# Schematic.net
KiCad netlist of a schematic drawn in Altium Designer
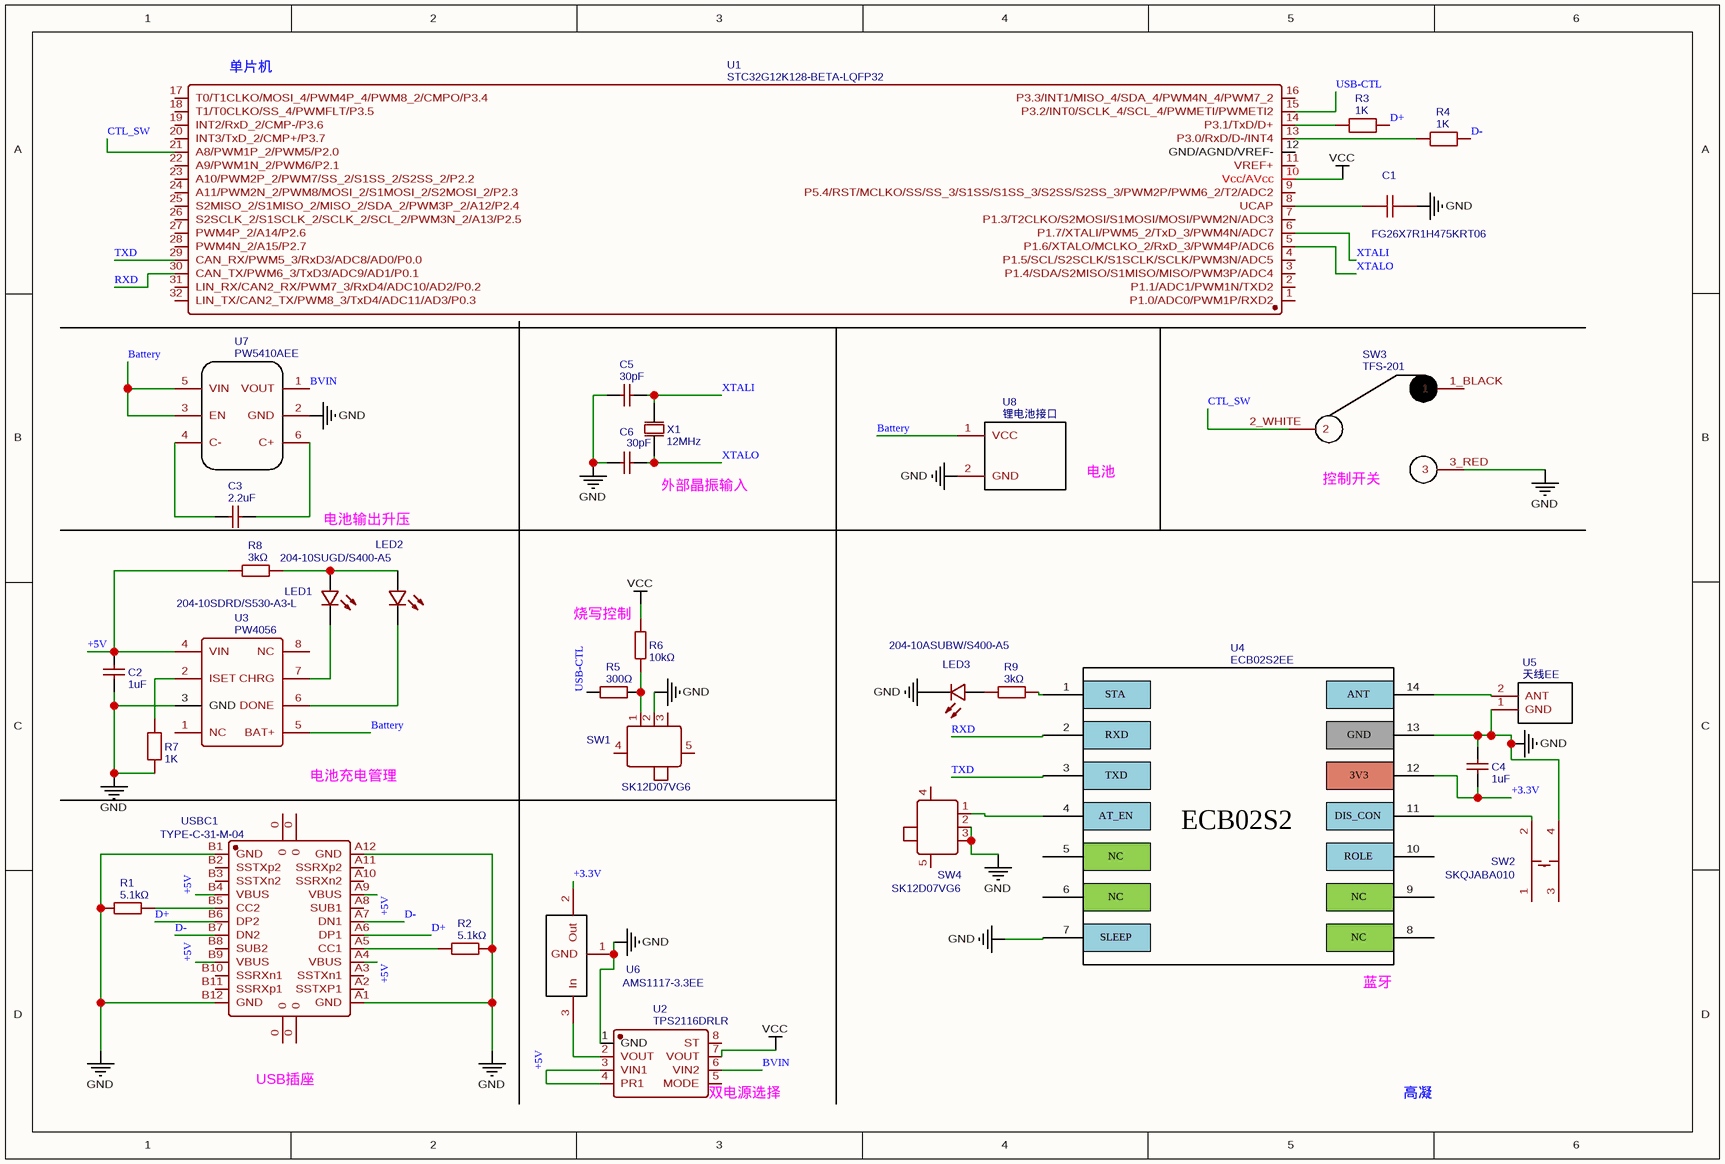
[diagram p0: Schematic原理图.schdoc]

(export (version "E")
  (design (tool "Eeschema 10.0.6"))
  (components
    (comp (ref "C1")
      (value "FG26X7R1H475KRT06")
      (fields (field (name "BOM_SUPPLIER PART") "C1620752") (field (name "CONTRIBUTOR") "LCSC"))
      (libsource (lib "altium-import") (part "root_0_FG26X7R1H475KRT06_"))
    )
    (comp (ref "C2")
      (value "1uF")
      (fields
        (field (name "BOM_MANUFACTURER PART") "CT4-0805B105K500F3")
        (field (name "BOM_SUPPLIER PART") "C94708")
        (field (name "CONTRIBUTOR") "LCSC")
      )
      (libsource (lib "altium-import") (part "root_1_1uF_"))
    )
    (comp (ref "C3")
      (value "2.2uF")
      (fields
        (field (name "BOM_SUPPLIER PART") "C263178")
        (field (name "BOM_MANUFACTURER PART") "CD1E225KC9BER1E000")
        (field (name "CONTRIBUTOR") "LCSC")
      )
      (libsource (lib "altium-import") (part "root_0_2.2uF_"))
    )
    (comp (ref "C4")
      (value "1uF")
      (fields
        (field (name "BOM_MANUFACTURER PART") "CT4-0805B105K500F3")
        (field (name "BOM_SUPPLIER PART") "C94708")
        (field (name "CONTRIBUTOR") "LCSC")
      )
      (libsource (lib "altium-import") (part "root_1_1uF_"))
    )
    (comp (ref "C5")
      (value "30pF")
      (fields
        (field (name "BOM_SUPPLIER PART") "C263194")
        (field (name "BOM_MANUFACTURER PART") "CD1H300JC94ECHD000")
        (field (name "CONTRIBUTOR") "LCSC")
      )
      (libsource (lib "altium-import") (part "root_0_30pF_"))
    )
    (comp (ref "C6")
      (value "30pF")
      (fields
        (field (name "BOM_SUPPLIER PART") "C263194")
        (field (name "BOM_MANUFACTURER PART") "CD1H300JC94ECHD000")
        (field (name "CONTRIBUTOR") "LCSC")
      )
      (libsource (lib "altium-import") (part "root_2_30pF_"))
    )
    (comp (ref "LED1")
      (value "204-10SDRD/S530-A3-L")
      (fields (field (name "BOM_SUPPLIER PART") "C84774"))
      (libsource (lib "altium-import") (part "root_3_204-10SDRD/S530-A3-L_"))
    )
    (comp (ref "LED2")
      (value "204-10SUGD/S400-A5")
      (fields (field (name "BOM_SUPPLIER PART") "C99761"))
      (libsource (lib "altium-import") (part "root_3_204-10SUGD/S400-A5_"))
    )
    (comp (ref "LED3")
      (value "204-10ASUBW/S400-A5")
      (fields (field (name "BOM_SUPPLIER PART") "C97696"))
      (libsource (lib "altium-import") (part "root_2_204-10ASUBW/S400-A5_"))
    )
    (comp (ref "R1")
      (value "5.1kΩ")
      (fields
        (field (name "BOM_SUPPLIER PART") "C119887")
        (field (name "BOM_MANUFACTURER PART") "CF1/6W-5.1KΩ±5% T")
        (field (name "CONTRIBUTOR") "LCSC")
      )
      (libsource (lib "altium-import") (part "root_0_5.1kΩ_"))
    )
    (comp (ref "R2")
      (value "5.1kΩ")
      (fields
        (field (name "BOM_SUPPLIER PART") "C119887")
        (field (name "BOM_MANUFACTURER PART") "CF1/6W-5.1KΩ±5% T")
        (field (name "CONTRIBUTOR") "LCSC")
      )
      (libsource (lib "altium-import") (part "root_0_5.1kΩ_"))
    )
    (comp (ref "R3")
      (value "1K")
      (fields
        (field (name "BOM_SUPPLIER PART") "C2979794")
        (field (name "BOM_MANUFACTURER PART") "MRS25000C1001FCT00")
        (field (name "CONTRIBUTOR") "lcsc")
      )
      (libsource (lib "altium-import") (part "root_2_1K_"))
    )
    (comp (ref "R4")
      (value "1K")
      (fields
        (field (name "BOM_SUPPLIER PART") "C2979794")
        (field (name "BOM_MANUFACTURER PART") "MRS25000C1001FCT00")
        (field (name "CONTRIBUTOR") "lcsc")
      )
      (libsource (lib "altium-import") (part "root_2_1K_"))
    )
    (comp (ref "R5")
      (value "300Ω")
      (fields
        (field (name "BOM_MANUFACTURER PART") "MFR0W4F3000A50")
        (field (name "BOM_SUPPLIER PART") "C58609")
      )
      (libsource (lib "altium-import") (part "root_0_300Ω_"))
    )
    (comp (ref "R6")
      (value "10kΩ")
      (fields
        (field (name "BOM_SUPPLIER PART") "C2843070")
        (field (name "BOM_MANUFACTURER PART") "MO2WS-10K±5%-6T63")
        (field (name "CONTRIBUTOR") "lcsc")
      )
      (libsource (lib "altium-import") (part "root_1_10kΩ_"))
    )
    (comp (ref "R7")
      (value "1K")
      (fields
        (field (name "BOM_SUPPLIER PART") "C2979794")
        (field (name "BOM_MANUFACTURER PART") "MRS25000C1001FCT00")
        (field (name "CONTRIBUTOR") "lcsc")
      )
      (libsource (lib "altium-import") (part "root_1_1K_"))
    )
    (comp (ref "R8")
      (value "3kΩ")
      (fields
        (field (name "BOM_SUPPLIER PART") "C119881")
        (field (name "BOM_MANUFACTURER PART") "CF1/6W-3KΩ±5% T")
        (field (name "CONTRIBUTOR") "LCSC")
      )
      (libsource (lib "altium-import") (part "root_0_3kΩ_"))
    )
    (comp (ref "R9")
      (value "3kΩ")
      (fields
        (field (name "BOM_SUPPLIER PART") "C119881")
        (field (name "BOM_MANUFACTURER PART") "CF1/6W-3KΩ±5% T")
        (field (name "CONTRIBUTOR") "LCSC")
      )
      (libsource (lib "altium-import") (part "root_0_3kΩ_"))
    )
    (comp (ref "SW1")
      (value "SK12D07VG6")
      (fields (field (name "BOM_SUPPLIER PART") "C2681575") (field (name "CONTRIBUTOR") "LCSC"))
      (libsource (lib "altium-import") (part "root_0_SK12D07VG6_"))
    )
    (comp (ref "SW2")
      (value "SKQJABA010")
      (fields (field (name "BOM_SUPPLIER PART") "C125037") (field (name "CONTRIBUTOR") "LCSC"))
      (libsource (lib "altium-import") (part "root_1_SKQJABA010_"))
    )
    (comp (ref "SW3")
      (value "TFS-201")
      (fields (field (name "CONTRIBUTOR") "watcem"))
      (libsource (lib "altium-import") (part "root_0_TFS-201_"))
    )
    (comp (ref "SW4")
      (value "SK12D07VG6")
      (fields (field (name "BOM_SUPPLIER PART") "C2681575") (field (name "CONTRIBUTOR") "LCSC"))
      (libsource (lib "altium-import") (part "root_3_SK12D07VG6_"))
    )
    (comp (ref "U1")
      (value "STC32G12K128-BETA-LQFP32")
      (fields
        (field (name "BOM_SUPPLIER PART") "C3020369")
        (field (name "BOM_MANUFACTURER PART") "STC32G12K128-Beta-LQFP32")
        (field (name "CONTRIBUTOR") "lcsc")
      )
      (libsource (lib "altium-import") (part "root_2_STC32G12K128-BETA-LQFP32_"))
    )
    (comp (ref "U2")
      (value "TPS2116DRLR")
      (fields (field (name "BOM_SUPPLIER PART") "C3235557") (field (name "CONTRIBUTOR") "lcsc"))
      (libsource (lib "altium-import") (part "root_0_TPS2116DRLR_"))
    )
    (comp (ref "U3")
      (value "PW4056")
      (fields (field (name "CONTRIBUTOR") "Poyzb"))
      (libsource (lib "altium-import") (part "root_0_PW4056_"))
    )
    (comp (ref "U4")
      (value "ECB02S2EE")
      (fields (field (name "CONTRIBUTOR") "fenghongchang"))
      (libsource (lib "altium-import") (part "root_0_ECB02S2EE_"))
    )
    (comp (ref "U5")
      (value "天线EE")
      (fields (field (name "CONTRIBUTOR") "pofeiren"))
      (libsource (lib "altium-import") (part "root_0_天线EE_"))
    )
    (comp (ref "U6")
      (value "AMS1117-3.3EE")
      (fields
        (field (name "BOM_SUPPLIER PART") "C6186")
        (field (name "BOM_MANUFACTURER PART") "AMS1117-3.3")
        (field (name "CONTRIBUTOR") "whg1998")
      )
      (libsource (lib "altium-import") (part "root_1_AMS1117-3.3EE_"))
    )
    (comp (ref "U7")
      (value "PW5410AEE")
      (fields (field (name "CONTRIBUTOR") "yao_yuan"))
      (libsource (lib "altium-import") (part "root_0_PW5410AEE_"))
    )
    (comp (ref "U8")
      (value "锂电池接口")
      (fields (field (name "CONTRIBUTOR") "watcem"))
      (libsource (lib "altium-import") (part "root_0_锂电池接口_"))
    )
    (comp (ref "USBC1")
      (value "TYPE-C-31-M-04")
      (fields (field (name "BOM_SUPPLIER PART") "C129018") (field (name "CONTRIBUTOR") "LCSC"))
      (libsource (lib "altium-import") (part "root_0_TYPE-C-31-M-04_"))
    )
    (comp (ref "X1")
      (value "12MHz")
      (fields
        (field (name "BOM_SUPPLIER PART") "C114441")
        (field (name "BOM_MANUFACTURER PART") "X49SD12MSD2SI")
        (field (name "CONTRIBUTOR") "LCSC")
      )
      (libsource (lib "altium-import") (part "root_1_12MHz_"))
    )
  )
  (nets
    (net (code "1") (name "/+3.3V") (class "Default")
      (node (ref "C4") (pin "1") (pinfunction "1_1") (pintype "passive"))
      (node (ref "U4") (pin "12") (pinfunction "12_12") (pintype "passive"))
      (node (ref "U6") (pin "2") (pinfunction "Out_2") (pintype "passive"))
    )
    (net (code "2") (name "/+5V") (class "Default")
      (node (ref "C2") (pin "2") (pinfunction "2_2") (pintype "passive"))
      (node (ref "R8") (pin "1") (pinfunction "1_1") (pintype "passive"))
      (node (ref "U2") (pin "3") (pinfunction "VIN1_3") (pintype "passive"))
      (node (ref "U2") (pin "4") (pinfunction "PR1_4") (pintype "passive"))
      (node (ref "U3") (pin "4") (pinfunction "VIN_4") (pintype "passive"))
      (node (ref "USBC1") (pin "A4") (pinfunction "VBUS_A4") (pintype "passive"))
      (node (ref "USBC1") (pin "A9") (pinfunction "VBUS_A9") (pintype "passive"))
      (node (ref "USBC1") (pin "B4") (pinfunction "VBUS_B4") (pintype "passive"))
      (node (ref "USBC1") (pin "B9") (pinfunction "VBUS_B9") (pintype "passive"))
    )
    (net (code "3") (name "/BVIN") (class "Default")
      (node (ref "U2") (pin "6") (pinfunction "VIN2_6") (pintype "passive"))
      (node (ref "U7") (pin "1") (pinfunction "VOUT_1") (pintype "passive"))
    )
    (net (code "4") (name "/Battery") (class "Default")
      (node (ref "U3") (pin "5") (pinfunction "BAT+_5") (pintype "passive"))
      (node (ref "U7") (pin "3") (pinfunction "EN_3") (pintype "passive"))
      (node (ref "U7") (pin "5") (pinfunction "VIN_5") (pintype "passive"))
      (node (ref "U8") (pin "1") (pinfunction "VCC_1") (pintype "passive"))
    )
    (net (code "5") (name "/CTL_SW") (class "Default")
      (node (ref "SW3") (pin "2_WHITE") (pinfunction "2_2_WHITE") (pintype "passive"))
      (node (ref "U1") (pin "21") (pinfunction "A8/PWM1P_2/PWM5/P2.0_21") (pintype "passive"))
    )
    (net (code "6") (name "/D+") (class "Default")
      (node (ref "R3") (pin "1") (pinfunction "1_1") (pintype "passive"))
      (node (ref "USBC1") (pin "A6") (pinfunction "DP1_A6") (pintype "passive"))
      (node (ref "USBC1") (pin "B6") (pinfunction "DP2_B6") (pintype "passive"))
    )
    (net (code "7") (name "/D-") (class "Default")
      (node (ref "R4") (pin "1") (pinfunction "1_1") (pintype "passive"))
      (node (ref "USBC1") (pin "A7") (pinfunction "DN1_A7") (pintype "passive"))
      (node (ref "USBC1") (pin "B7") (pinfunction "DN2_B7") (pintype "passive"))
    )
    (net (code "8") (name "/RXD") (class "Default")
      (node (ref "U1") (pin "30") (pinfunction "CAN_TX/PWM6_3/TxD3/ADC9/AD1/P0.1_30") (pintype "passive"))
      (node (ref "U4") (pin "2") (pinfunction "2_2") (pintype "passive"))
    )
    (net (code "9") (name "/TXD") (class "Default")
      (node (ref "U1") (pin "29") (pinfunction "CAN_RX/PWM5_3/RxD3/ADC8/AD0/P0.0_29") (pintype "passive"))
      (node (ref "U4") (pin "3") (pinfunction "3_3") (pintype "passive"))
    )
    (net (code "10") (name "/USB-CTL") (class "Default")
      (node (ref "R5") (pin "1") (pinfunction "1_1") (pintype "passive"))
      (node (ref "U1") (pin "15") (pinfunction "P3.2/INT0/SCLK_4/SCL_4/PWMETI/PWMETI2_15") (pintype "passive"))
    )
    (net (code "11") (name "/XTALI") (class "Default")
      (node (ref "C5") (pin "2") (pinfunction "2_2") (pintype "passive"))
      (node (ref "U1") (pin "6") (pinfunction "P1.7/XTALI/PWM5_2/TxD_3/PWM4N/ADC7_6") (pintype "passive"))
      (node (ref "X1") (pin "2") (pinfunction "OSC2_2") (pintype "passive"))
    )
    (net (code "12") (name "/XTALO") (class "Default")
      (node (ref "C6") (pin "1") (pinfunction "1_1") (pintype "passive"))
      (node (ref "U1") (pin "5") (pinfunction "P1.6/XTALO/MCLKO_2/RxD_3/PWM4P/ADC6_5") (pintype "passive"))
      (node (ref "X1") (pin "1") (pinfunction "OSC1_1") (pintype "passive"))
    )
    (net (code "13") (name "GND") (class "Default")
      (node (ref "C1") (pin "2") (pinfunction "2_2") (pintype "passive"))
      (node (ref "C2") (pin "1") (pinfunction "1_1") (pintype "passive"))
      (node (ref "C4") (pin "2") (pinfunction "2_2") (pintype "passive"))
      (node (ref "C5") (pin "1") (pinfunction "1_1") (pintype "passive"))
      (node (ref "C6") (pin "2") (pinfunction "2_2") (pintype "passive"))
      (node (ref "LED3") (pin "2") (pinfunction "K_2") (pintype "passive"))
      (node (ref "R1") (pin "1") (pinfunction "1_1") (pintype "passive"))
      (node (ref "R2") (pin "2") (pinfunction "2_2") (pintype "passive"))
      (node (ref "R7") (pin "1") (pinfunction "1_1") (pintype "passive"))
      (node (ref "SW1") (pin "2") (pinfunction "2_2") (pintype "passive"))
      (node (ref "SW2") (pin "4") (pinfunction "4_4") (pintype "passive"))
      (node (ref "SW3") (pin "3_RED") (pinfunction "3_3_RED") (pintype "passive"))
      (node (ref "SW4") (pin "2") (pinfunction "2_2") (pintype "passive"))
      (node (ref "SW4") (pin "3") (pinfunction "3_3") (pintype "passive"))
      (node (ref "U2") (pin "1") (pinfunction "GND_1") (pintype "passive"))
      (node (ref "U3") (pin "3") (pinfunction "GND_3") (pintype "passive"))
      (node (ref "U4") (pin "13") (pinfunction "13_13") (pintype "passive"))
      (node (ref "U4") (pin "7") (pinfunction "7_7") (pintype "passive"))
      (node (ref "U5") (pin "1") (pinfunction "GND_1") (pintype "passive"))
      (node (ref "U6") (pin "1") (pinfunction "GND_1") (pintype "passive"))
      (node (ref "U7") (pin "2") (pinfunction "GND_2") (pintype "passive"))
      (node (ref "U8") (pin "2") (pinfunction "GND_2") (pintype "passive"))
      (node (ref "USBC1") (pin "A1") (pinfunction "GND_A1") (pintype "passive"))
      (node (ref "USBC1") (pin "A12") (pinfunction "GND_A12") (pintype "passive"))
      (node (ref "USBC1") (pin "B1") (pinfunction "GND_B1") (pintype "passive"))
      (node (ref "USBC1") (pin "B12") (pinfunction "GND_B12") (pintype "passive"))
    )
    (net (code "14") (name "Net-(LED1-A)") (class "Default")
      (node (ref "LED1") (pin "1") (pinfunction "A_1") (pintype "passive"))
      (node (ref "LED2") (pin "1") (pinfunction "A_1") (pintype "passive"))
      (node (ref "R8") (pin "2") (pinfunction "2_2") (pintype "passive"))
    )
    (net (code "15") (name "Net-(LED1-C)") (class "Default")
      (node (ref "LED1") (pin "2") (pinfunction "C_2") (pintype "passive"))
      (node (ref "U3") (pin "7") (pinfunction "CHRG_7") (pintype "passive"))
    )
    (net (code "16") (name "Net-(LED2-K)") (class "Default")
      (node (ref "LED2") (pin "2") (pinfunction "K_2") (pintype "passive"))
      (node (ref "U3") (pin "6") (pinfunction "DONE_6") (pintype "passive"))
    )
    (net (code "17") (name "Net-(LED3-A)") (class "Default")
      (node (ref "LED3") (pin "1") (pinfunction "A_1") (pintype "passive"))
      (node (ref "R9") (pin "1") (pinfunction "1_1") (pintype "passive"))
    )
    (net (code "18") (name "Net-(R5-Pad2)") (class "Default")
      (node (ref "R5") (pin "2") (pinfunction "2_2") (pintype "passive"))
      (node (ref "R6") (pin "1") (pinfunction "1_1") (pintype "passive"))
      (node (ref "SW1") (pin "1") (pinfunction "1_1") (pintype "passive"))
    )
    (net (code "19") (name "Net-(R9-Pad2)") (class "Default")
      (node (ref "R9") (pin "2") (pinfunction "2_2") (pintype "passive"))
      (node (ref "U4") (pin "1") (pinfunction "1_1") (pintype "passive"))
    )
    (net (code "20") (name "Net-(SW2-Pad2)") (class "Default")
      (node (ref "SW2") (pin "2") (pinfunction "2_2") (pintype "passive"))
      (node (ref "U4") (pin "11") (pinfunction "11_11") (pintype "passive"))
    )
    (net (code "21") (name "Net-(SW4-Pad1)") (class "Default")
      (node (ref "SW4") (pin "1") (pinfunction "1_1") (pintype "passive"))
      (node (ref "U4") (pin "4") (pinfunction "4_4") (pintype "passive"))
    )
    (net (code "22") (name "Net-(U1-P3.0{slash}RxD{slash}D-{slash}INT4)") (class "Default")
      (node (ref "R4") (pin "2") (pinfunction "2_2") (pintype "passive"))
      (node (ref "U1") (pin "13") (pinfunction "P3.0/RxD/D-/INT4_13") (pintype "passive"))
    )
    (net (code "23") (name "Net-(U1-P3.1{slash}TxD{slash}D+)") (class "Default")
      (node (ref "R3") (pin "2") (pinfunction "2_2") (pintype "passive"))
      (node (ref "U1") (pin "14") (pinfunction "P3.1/TxD/D+_14") (pintype "passive"))
    )
    (net (code "24") (name "Net-(U1-UCAP)") (class "Default")
      (node (ref "C1") (pin "1") (pinfunction "1_1") (pintype "passive"))
      (node (ref "U1") (pin "8") (pinfunction "UCAP_8") (pintype "passive"))
    )
    (net (code "25") (name "Net-(U3-ISET)") (class "Default")
      (node (ref "R7") (pin "2") (pinfunction "2_2") (pintype "passive"))
      (node (ref "U3") (pin "2") (pinfunction "ISET_2") (pintype "passive"))
    )
    (net (code "26") (name "Net-(U5-ANT)") (class "Default")
      (node (ref "U4") (pin "14") (pinfunction "14_14") (pintype "passive"))
      (node (ref "U5") (pin "2") (pinfunction "ANT_2") (pintype "passive"))
    )
    (net (code "27") (name "Net-(U6-In)") (class "Default")
      (node (ref "U2") (pin "2") (pinfunction "VOUT_2") (pintype "passive"))
      (node (ref "U6") (pin "3") (pinfunction "In_3") (pintype "passive"))
    )
    (net (code "28") (name "Net-(U7-C+)") (class "Default")
      (node (ref "C3") (pin "2") (pinfunction "2_2") (pintype "passive"))
      (node (ref "U7") (pin "6") (pinfunction "C+_6") (pintype "passive"))
    )
    (net (code "29") (name "Net-(U7-C-)") (class "Default")
      (node (ref "C3") (pin "1") (pinfunction "1_1") (pintype "passive"))
      (node (ref "U7") (pin "4") (pinfunction "C-_4") (pintype "passive"))
    )
    (net (code "30") (name "Net-(USBC1-CC1)") (class "Default")
      (node (ref "R2") (pin "1") (pinfunction "1_1") (pintype "passive"))
      (node (ref "USBC1") (pin "A5") (pinfunction "CC1_A5") (pintype "passive"))
    )
    (net (code "31") (name "Net-(USBC1-CC2)") (class "Default")
      (node (ref "R1") (pin "2") (pinfunction "2_2") (pintype "passive"))
      (node (ref "USBC1") (pin "B5") (pinfunction "CC2_B5") (pintype "passive"))
    )
    (net (code "32") (name "VCC") (class "Default")
      (node (ref "R6") (pin "2") (pinfunction "2_2") (pintype "passive"))
      (node (ref "U1") (pin "10") (pinfunction "Vcc/AVcc_10") (pintype "passive"))
      (node (ref "U2") (pin "7") (pinfunction "VOUT_7") (pintype "passive"))
    )
    (net (code "33") (name "unconnected-(SW1-Pad3)") (class "Default")
      (node (ref "SW1") (pin "3") (pinfunction "3_3") (pintype "passive"))
    )
    (net (code "34") (name "unconnected-(SW1-Pad4)") (class "Default")
      (node (ref "SW1") (pin "4") (pinfunction "4_4") (pintype "passive"))
    )
    (net (code "35") (name "unconnected-(SW1-Pad5)") (class "Default")
      (node (ref "SW1") (pin "5") (pinfunction "5_5") (pintype "passive"))
    )
    (net (code "36") (name "unconnected-(SW2-Pad1)") (class "Default")
      (node (ref "SW2") (pin "1") (pinfunction "1_1") (pintype "passive"))
    )
    (net (code "37") (name "unconnected-(SW2-Pad3)") (class "Default")
      (node (ref "SW2") (pin "3") (pinfunction "3_3") (pintype "passive"))
    )
    (net (code "38") (name "unconnected-(SW3-1-Pad1_BLACK)") (class "Default")
      (node (ref "SW3") (pin "1_BLACK") (pinfunction "1_1_BLACK") (pintype "passive"))
    )
    (net (code "39") (name "unconnected-(SW4-Pad4)") (class "Default")
      (node (ref "SW4") (pin "4") (pinfunction "4_4") (pintype "passive"))
    )
    (net (code "40") (name "unconnected-(SW4-Pad5)") (class "Default")
      (node (ref "SW4") (pin "5") (pinfunction "5_5") (pintype "passive"))
    )
    (net (code "41") (name "unconnected-(U1-A9{slash}PWM1N_2{slash}PWM6{slash}P2.1-Pad22)") (class "Default")
      (node (ref "U1") (pin "22") (pinfunction "A9/PWM1N_2/PWM6/P2.1_22") (pintype "passive"))
    )
    (net (code "42") (name "unconnected-(U1-A10{slash}PWM2P_2{slash}PWM7{slash}SS_2{slash}S1SS_2{slash}S2SS_2{slash}P2.2-Pad23)") (class "Default")
      (node (ref "U1") (pin "23") (pinfunction "A10/PWM2P_2/PWM7/SS_2/S1SS_2/S2SS_2/P2.2_23") (pintype "passive"))
    )
    (net (code "43") (name "unconnected-(U1-A11{slash}PWM2N_2{slash}PWM8{slash}MOSI_2{slash}S1MOSI_2{slash}S2MOSI_2{slash}P2.3-Pad24)") (class "Default")
      (node (ref "U1") (pin "24") (pinfunction "A11/PWM2N_2/PWM8/MOSI_2/S1MOSI_2/S2MOSI_2/P2.3_24") (pintype "passive"))
    )
    (net (code "44") (name "unconnected-(U1-GND{slash}AGND{slash}VREF--Pad12)") (class "Default")
      (node (ref "U1") (pin "12") (pinfunction "GND/AGND/VREF-_12") (pintype "passive"))
    )
    (net (code "45") (name "unconnected-(U1-INT2{slash}RxD_2{slash}CMP-{slash}P3.6-Pad19)") (class "Default")
      (node (ref "U1") (pin "19") (pinfunction "INT2/RxD_2/CMP-/P3.6_19") (pintype "passive"))
    )
    (net (code "46") (name "unconnected-(U1-INT3{slash}TxD_2{slash}CMP+{slash}P3.7-Pad20)") (class "Default")
      (node (ref "U1") (pin "20") (pinfunction "INT3/TxD_2/CMP+/P3.7_20") (pintype "passive"))
    )
    (net (code "47") (name "unconnected-(U1-LIN_RX{slash}CAN2_RX{slash}PWM7_3{slash}RxD4{slash}ADC10{slash}AD2{slash}P0.2-Pad31)") (class "Default")
      (node (ref "U1") (pin "31") (pinfunction "LIN_RX/CAN2_RX/PWM7_3/RxD4/ADC10/AD2/P0.2_31") (pintype "passive"))
    )
    (net (code "48") (name "unconnected-(U1-LIN_TX{slash}CAN2_TX{slash}PWM8_3{slash}TxD4{slash}ADC11{slash}AD3{slash}P0.3-Pad32)") (class "Default")
      (node (ref "U1") (pin "32") (pinfunction "LIN_TX/CAN2_TX/PWM8_3/TxD4/ADC11/AD3/P0.3_32") (pintype "passive"))
    )
    (net (code "49") (name "unconnected-(U1-P1.0{slash}ADC0{slash}PWM1P{slash}RXD2-Pad1)") (class "Default")
      (node (ref "U1") (pin "1") (pinfunction "P1.0/ADC0/PWM1P/RXD2_1") (pintype "passive"))
    )
    (net (code "50") (name "unconnected-(U1-P1.1{slash}ADC1{slash}PWM1N{slash}TXD2-Pad2)") (class "Default")
      (node (ref "U1") (pin "2") (pinfunction "P1.1/ADC1/PWM1N/TXD2_2") (pintype "passive"))
    )
    (net (code "51") (name "unconnected-(U1-P1.3{slash}T2CLKO{slash}S2MOSI{slash}S1MOSI{slash}MOSI{slash}PWM2N{slash}ADC3-Pad7)") (class "Default")
      (node (ref "U1") (pin "7") (pinfunction "P1.3/T2CLKO/S2MOSI/S1MOSI/MOSI/PWM2N/ADC3_7") (pintype "passive"))
    )
    (net (code "52") (name "unconnected-(U1-P1.4{slash}SDA{slash}S2MISO{slash}S1MISO{slash}MISO{slash}PWM3P{slash}ADC4-Pad3)") (class "Default")
      (node (ref "U1") (pin "3") (pinfunction "P1.4/SDA/S2MISO/S1MISO/MISO/PWM3P/ADC4_3") (pintype "passive"))
    )
    (net (code "53") (name "unconnected-(U1-P1.5{slash}SCL{slash}S2SCLK{slash}S1SCLK{slash}SCLK{slash}PWM3N{slash}ADC5-Pad4)") (class "Default")
      (node (ref "U1") (pin "4") (pinfunction "P1.5/SCL/S2SCLK/S1SCLK/SCLK/PWM3N/ADC5_4") (pintype "passive"))
    )
    (net (code "54") (name "unconnected-(U1-P3.3{slash}INT1{slash}MISO_4{slash}SDA_4{slash}PWM4N_4{slash}PWM7_2-Pad16)") (class "Default")
      (node (ref "U1") (pin "16") (pinfunction "P3.3/INT1/MISO_4/SDA_4/PWM4N_4/PWM7_2_16") (pintype "passive"))
    )
    (net (code "55") (name "unconnected-(U1-P5.4{slash}RST{slash}MCLKO{slash}SS{slash}SS_3{slash}S1SS{slash}S1SS_3{slash}S2SS{slash}S2SS_3{slash}PWM2P{slash}PWM6_2{slash}T2{slash}ADC2-Pad9)") (class "Default")
      (node (ref "U1") (pin "9") (pinfunction "P5.4/RST/MCLKO/SS/SS_3/S1SS/S1SS_3/S2SS/S2SS_3/PWM2P/PWM6_2/T2/ADC2_9") (pintype "passive"))
    )
    (net (code "56") (name "unconnected-(U1-PWM4N_2{slash}A15{slash}P2.7-Pad28)") (class "Default")
      (node (ref "U1") (pin "28") (pinfunction "PWM4N_2/A15/P2.7_28") (pintype "passive"))
    )
    (net (code "57") (name "unconnected-(U1-PWM4P_2{slash}A14{slash}P2.6-Pad27)") (class "Default")
      (node (ref "U1") (pin "27") (pinfunction "PWM4P_2/A14/P2.6_27") (pintype "passive"))
    )
    (net (code "58") (name "unconnected-(U1-S2MISO_2{slash}S1MISO_2{slash}MISO_2{slash}SDA_2{slash}PWM3P_2{slash}A12{slash}P2.4-Pad25)") (class "Default")
      (node (ref "U1") (pin "25") (pinfunction "S2MISO_2/S1MISO_2/MISO_2/SDA_2/PWM3P_2/A12/P2.4_25") (pintype "passive"))
    )
    (net (code "59") (name "unconnected-(U1-S2SCLK_2{slash}S1SCLK_2{slash}SCLK_2{slash}SCL_2{slash}PWM3N_2{slash}A13{slash}P2.5-Pad26)") (class "Default")
      (node (ref "U1") (pin "26") (pinfunction "S2SCLK_2/S1SCLK_2/SCLK_2/SCL_2/PWM3N_2/A13/P2.5_26") (pintype "passive"))
    )
    (net (code "60") (name "unconnected-(U1-T0{slash}T1CLKO{slash}MOSI_4{slash}PWM4P_4{slash}PWM8_2{slash}CMPO{slash}P3.4-Pad17)") (class "Default")
      (node (ref "U1") (pin "17") (pinfunction "T0/T1CLKO/MOSI_4/PWM4P_4/PWM8_2/CMPO/P3.4_17") (pintype "passive"))
    )
    (net (code "61") (name "unconnected-(U1-T1{slash}T0CLKO{slash}SS_4{slash}PWMFLT{slash}P3.5-Pad18)") (class "Default")
      (node (ref "U1") (pin "18") (pinfunction "T1/T0CLKO/SS_4/PWMFLT/P3.5_18") (pintype "passive"))
    )
    (net (code "62") (name "unconnected-(U1-VREF+-Pad11)") (class "Default")
      (node (ref "U1") (pin "11") (pinfunction "VREF+_11") (pintype "passive"))
    )
    (net (code "63") (name "unconnected-(U2-MODE-Pad5)") (class "Default")
      (node (ref "U2") (pin "5") (pinfunction "MODE_5") (pintype "passive"))
    )
    (net (code "64") (name "unconnected-(U2-ST-Pad8)") (class "Default")
      (node (ref "U2") (pin "8") (pinfunction "ST_8") (pintype "passive"))
    )
    (net (code "65") (name "unconnected-(U3-NC-Pad1)") (class "Default")
      (node (ref "U3") (pin "1") (pinfunction "NC_1") (pintype "passive"))
    )
    (net (code "66") (name "unconnected-(U3-NC-Pad8)") (class "Default")
      (node (ref "U3") (pin "8") (pinfunction "NC_8") (pintype "passive"))
    )
    (net (code "67") (name "unconnected-(U4-Pad5)") (class "Default")
      (node (ref "U4") (pin "5") (pinfunction "5_5") (pintype "passive"))
    )
    (net (code "68") (name "unconnected-(U4-Pad6)") (class "Default")
      (node (ref "U4") (pin "6") (pinfunction "6_6") (pintype "passive"))
    )
    (net (code "69") (name "unconnected-(U4-Pad8)") (class "Default")
      (node (ref "U4") (pin "8") (pinfunction "8_8") (pintype "passive"))
    )
    (net (code "70") (name "unconnected-(U4-Pad9)") (class "Default")
      (node (ref "U4") (pin "9") (pinfunction "9_9") (pintype "passive"))
    )
    (net (code "71") (name "unconnected-(U4-Pad10)") (class "Default")
      (node (ref "U4") (pin "10") (pinfunction "10_10") (pintype "passive"))
    )
    (net (code "72") (name "unconnected-(USBC1-Pad0)") (class "Default")
      (node (ref "USBC1") (pin "0") (pinfunction "0_0") (pintype "passive"))
    )
    (net (code "73") (name "unconnected-(USBC1-Pad0)_1") (class "Default")
      (node (ref "USBC1") (pin "0") (pinfunction "0_0") (pintype "passive"))
    )
    (net (code "74") (name "unconnected-(USBC1-Pad0)_2") (class "Default")
      (node (ref "USBC1") (pin "0") (pinfunction "0_0") (pintype "passive"))
    )
    (net (code "75") (name "unconnected-(USBC1-Pad0)_3") (class "Default")
      (node (ref "USBC1") (pin "0") (pinfunction "0_0") (pintype "passive"))
    )
    (net (code "76") (name "unconnected-(USBC1-SSRXn1-PadB10)") (class "Default")
      (node (ref "USBC1") (pin "B10") (pinfunction "SSRXn1_B10") (pintype "passive"))
    )
    (net (code "77") (name "unconnected-(USBC1-SSRXn2-PadA10)") (class "Default")
      (node (ref "USBC1") (pin "A10") (pinfunction "SSRXn2_A10") (pintype "passive"))
    )
    (net (code "78") (name "unconnected-(USBC1-SSRXp1-PadB11)") (class "Default")
      (node (ref "USBC1") (pin "B11") (pinfunction "SSRXp1_B11") (pintype "passive"))
    )
    (net (code "79") (name "unconnected-(USBC1-SSRXp2-PadA11)") (class "Default")
      (node (ref "USBC1") (pin "A11") (pinfunction "SSRXp2_A11") (pintype "passive"))
    )
    (net (code "80") (name "unconnected-(USBC1-SSTXP1-PadA2)") (class "Default")
      (node (ref "USBC1") (pin "A2") (pinfunction "SSTXP1_A2") (pintype "passive"))
    )
    (net (code "81") (name "unconnected-(USBC1-SSTXn1-PadA3)") (class "Default")
      (node (ref "USBC1") (pin "A3") (pinfunction "SSTXn1_A3") (pintype "passive"))
    )
    (net (code "82") (name "unconnected-(USBC1-SSTXn2-PadB3)") (class "Default")
      (node (ref "USBC1") (pin "B3") (pinfunction "SSTXn2_B3") (pintype "passive"))
    )
    (net (code "83") (name "unconnected-(USBC1-SSTXp2-PadB2)") (class "Default")
      (node (ref "USBC1") (pin "B2") (pinfunction "SSTXp2_B2") (pintype "passive"))
    )
    (net (code "84") (name "unconnected-(USBC1-SUB1-PadA8)") (class "Default")
      (node (ref "USBC1") (pin "A8") (pinfunction "SUB1_A8") (pintype "passive"))
    )
    (net (code "85") (name "unconnected-(USBC1-SUB2-PadB8)") (class "Default")
      (node (ref "USBC1") (pin "B8") (pinfunction "SUB2_B8") (pintype "passive"))
    )
  )
)
